# LCDTFT_FPC40P_SPI4_3_2INCH_CTP.net
KiCad netlist of a schematic drawn in Altium Designer
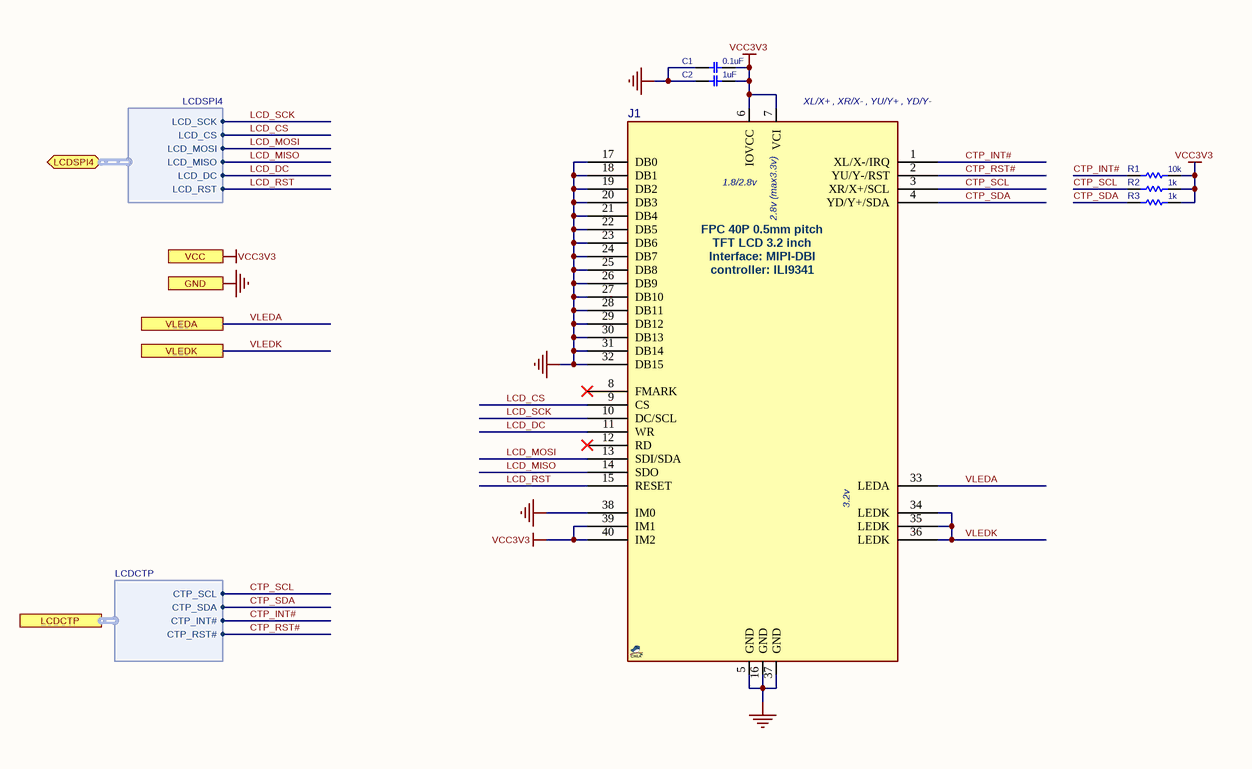
[diagram p0: LCDTFT_FPC40P_SPI4_3.2INCH_CTP.SchDoc]

(export (version "E")
  (design (tool "Eeschema 10.0.6"))
  (components
    (comp (ref "C1")
      (value "0.1uF")
      (footprint "C0402")
      (description "CAP, MLCC")
      (fields (field (name "MANF_P#") "GRM155R71H104KE14D") (field (name "MANF") "Murata"))
      (libsource (lib "passive_smd") (part "CAP_SMD_MLCC"))
    )
    (comp (ref "C2")
      (value "1uF")
      (footprint "C0402")
      (description "CAP, MLCC")
      (libsource (lib "passive_smd") (part "CAP_SMD_MLCC"))
    )
    (comp (ref "J1")
      (value "FPC50_40")
      (footprint "FPC50_40T")
      (description "LCD TFT Color, FPC40P, 3.2\" with touch")
      (fields (field (name "MANF") "Hirose") (field (name "MANF_P#") "FH12A-40S-0.5SH"))
      (libsource (lib "lcdtft") (part "LCDTFT_DBI_FPC40P_3.2INCH"))
    )
    (comp (ref "R1")
      (value "10k")
      (footprint "R0402")
      (description "RESISTOR, SMD")
      (libsource (lib "passive_res_smd") (part "RES_SMD"))
    )
    (comp (ref "R2")
      (value "1k")
      (footprint "R0402")
      (description "RESISTOR, SMD")
      (libsource (lib "passive_res_smd") (part "RES_SMD"))
    )
    (comp (ref "R3")
      (value "1k")
      (footprint "R0402")
      (description "RESISTOR, SMD")
      (libsource (lib "passive_res_smd") (part "RES_SMD"))
    )
  )
  (nets
    (net (code "3") (name "/CTP_INT#") (class "Default")
      (node (ref "J1") (pin "1") (pinfunction "XL/X-/IRQ_1") (pintype "passive"))
      (node (ref "R1") (pin "1") (pinfunction "1_1") (pintype "passive"))
    )
    (net (code "4") (name "/CTP_RST#") (class "Default")
      (node (ref "J1") (pin "2") (pinfunction "YU/Y-/RST_2") (pintype "passive"))
    )
    (net (code "5") (name "/CTP_SCL") (class "Default")
      (node (ref "J1") (pin "3") (pinfunction "XR/X+/SCL_3") (pintype "passive"))
      (node (ref "R2") (pin "1") (pinfunction "1_1") (pintype "passive"))
    )
    (net (code "6") (name "/CTP_SDA") (class "Default")
      (node (ref "J1") (pin "4") (pinfunction "YD/Y+/SDA_4") (pintype "passive"))
      (node (ref "R3") (pin "1") (pinfunction "1_1") (pintype "passive"))
    )
    (net (code "7") (name "/LCD_CS") (class "Default")
      (node (ref "J1") (pin "9") (pinfunction "CS_9") (pintype "passive"))
    )
    (net (code "8") (name "/LCD_DC") (class "Default")
      (node (ref "J1") (pin "11") (pinfunction "WR_11") (pintype "passive"))
    )
    (net (code "9") (name "/LCD_MISO") (class "Default")
      (node (ref "J1") (pin "14") (pinfunction "SDO_14") (pintype "passive"))
    )
    (net (code "10") (name "/LCD_MOSI") (class "Default")
      (node (ref "J1") (pin "13") (pinfunction "SDI/SDA_13") (pintype "passive"))
    )
    (net (code "11") (name "/LCD_RST") (class "Default")
      (node (ref "J1") (pin "15") (pinfunction "RESET_15") (pintype "passive"))
    )
    (net (code "12") (name "/LCD_SCK") (class "Default")
      (node (ref "J1") (pin "10") (pinfunction "DC/SCL_10") (pintype "passive"))
    )
    (net (code "13") (name "/VLEDA") (class "Default")
      (node (ref "J1") (pin "33") (pinfunction "LEDA_33") (pintype "passive"))
    )
    (net (code "14") (name "/VLEDK") (class "Default")
      (node (ref "J1") (pin "34") (pinfunction "LEDK_34") (pintype "passive"))
      (node (ref "J1") (pin "35") (pinfunction "LEDK_35") (pintype "passive"))
      (node (ref "J1") (pin "36") (pinfunction "LEDK_36") (pintype "passive"))
    )
    (net (code "17") (name "GND") (class "Default")
      (node (ref "C1") (pin "2") (pinfunction "2_2") (pintype "passive"))
      (node (ref "C2") (pin "2") (pinfunction "2_2") (pintype "passive"))
      (node (ref "J1") (pin "16") (pinfunction "GND_16") (pintype "passive"))
      (node (ref "J1") (pin "17") (pinfunction "DB0_17") (pintype "passive"))
      (node (ref "J1") (pin "18") (pinfunction "DB1_18") (pintype "passive"))
      (node (ref "J1") (pin "19") (pinfunction "DB2_19") (pintype "passive"))
      (node (ref "J1") (pin "20") (pinfunction "DB3_20") (pintype "passive"))
      (node (ref "J1") (pin "21") (pinfunction "DB4_21") (pintype "passive"))
      (node (ref "J1") (pin "22") (pinfunction "DB5_22") (pintype "passive"))
      (node (ref "J1") (pin "23") (pinfunction "DB6_23") (pintype "passive"))
      (node (ref "J1") (pin "24") (pinfunction "DB7_24") (pintype "passive"))
      (node (ref "J1") (pin "25") (pinfunction "DB8_25") (pintype "passive"))
      (node (ref "J1") (pin "26") (pinfunction "DB9_26") (pintype "passive"))
      (node (ref "J1") (pin "27") (pinfunction "DB10_27") (pintype "passive"))
      (node (ref "J1") (pin "28") (pinfunction "DB11_28") (pintype "passive"))
      (node (ref "J1") (pin "29") (pinfunction "DB12_29") (pintype "passive"))
      (node (ref "J1") (pin "30") (pinfunction "DB13_30") (pintype "passive"))
      (node (ref "J1") (pin "31") (pinfunction "DB14_31") (pintype "passive"))
      (node (ref "J1") (pin "32") (pinfunction "DB15_32") (pintype "passive"))
      (node (ref "J1") (pin "37") (pinfunction "GND_37") (pintype "passive"))
      (node (ref "J1") (pin "38") (pinfunction "IM0_38") (pintype "passive"))
      (node (ref "J1") (pin "5") (pinfunction "GND_5") (pintype "passive"))
    )
    (net (code "18") (name "VCC3V3") (class "Default")
      (node (ref "C1") (pin "1") (pinfunction "1_1") (pintype "passive"))
      (node (ref "C2") (pin "1") (pinfunction "1_1") (pintype "passive"))
      (node (ref "J1") (pin "39") (pinfunction "IM1_39") (pintype "passive"))
      (node (ref "J1") (pin "40") (pinfunction "IM2_40") (pintype "passive"))
      (node (ref "J1") (pin "6") (pinfunction "IOVCC_6") (pintype "passive"))
      (node (ref "J1") (pin "7") (pinfunction "VCI_7") (pintype "passive"))
      (node (ref "R1") (pin "2") (pinfunction "2_2") (pintype "passive"))
      (node (ref "R2") (pin "2") (pinfunction "2_2") (pintype "passive"))
      (node (ref "R3") (pin "2") (pinfunction "2_2") (pintype "passive"))
    )
    (net (code "19") (name "unconnected-(J1-FMARK-Pad8)") (class "Default")
      (node (ref "J1") (pin "8") (pinfunction "FMARK_8") (pintype "passive+no_connect"))
    )
    (net (code "20") (name "unconnected-(J1-RD-Pad12)") (class "Default")
      (node (ref "J1") (pin "12") (pinfunction "RD_12") (pintype "passive+no_connect"))
    )
  )
)
